# Lab6.net
KiCad netlist of a schematic drawn in Altium Designer
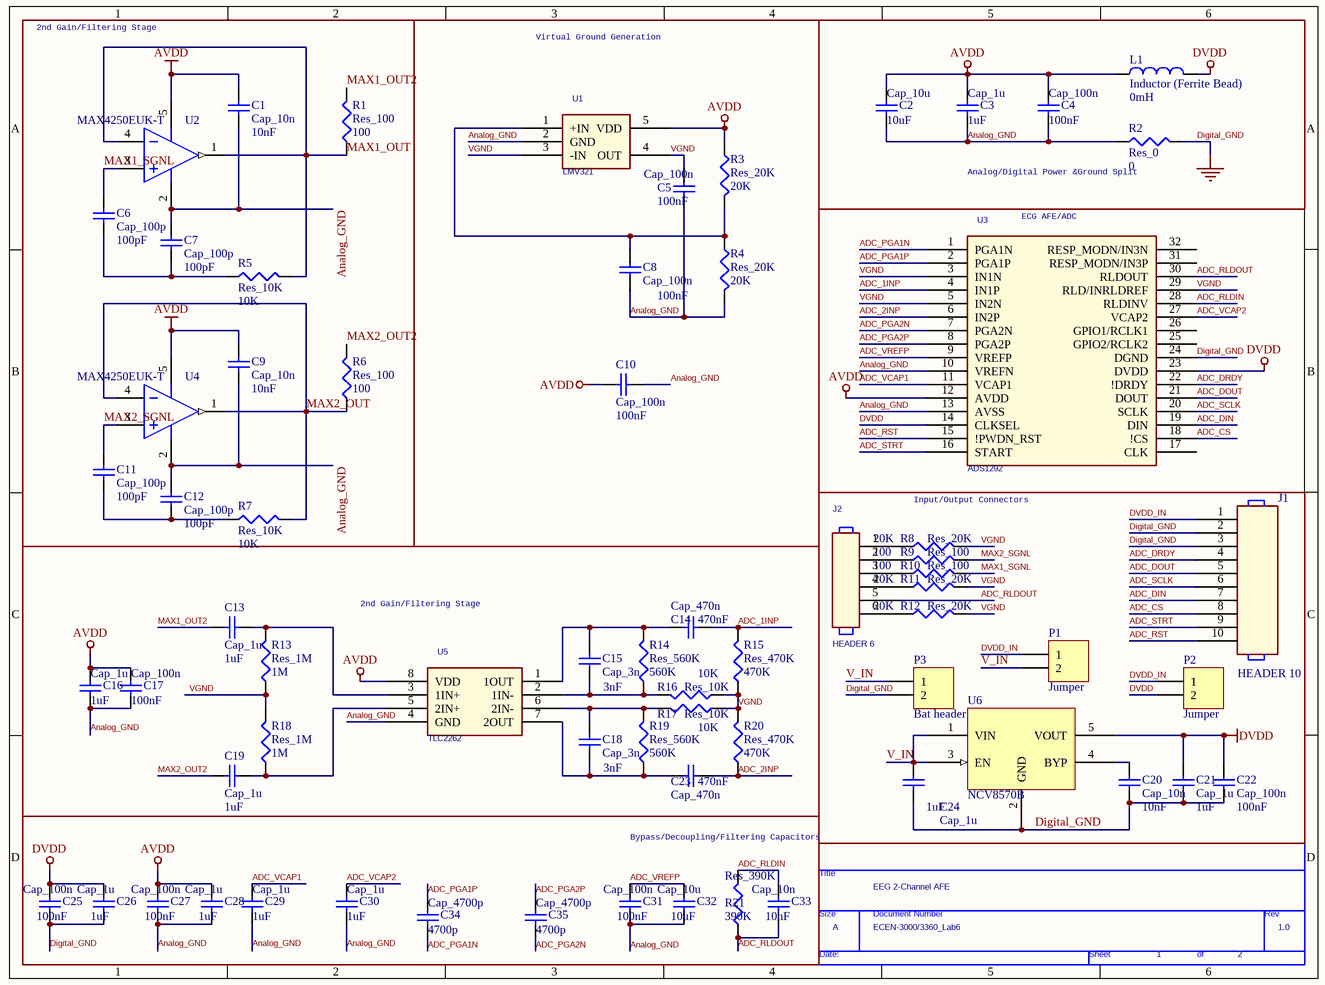
[diagram p0: Lab6.SchDoc]

(export (version "E")
  (design (tool "Eeschema 10.0.6"))
  (components
    (comp (ref "*")
      (value "TitleBlock0")
      (fields
        (field (name "PAGE COUNT") "2")
        (field (name "PAGE NUMBER") "1")
        (field (name "PAGE SIZE") "A")
        (field (name "TITLE") "EEG 2-Channel AFE")
        (field (name "REVCODE") "1.0")
        (field (name "DOC") "ECEN-3000/3360_Lab6")
      )
      (libsource (lib "*") (part "TitleBlock0"))
    )
    (comp (ref "C1")
      (value "Cap_10n")
      (footprint "SMD_0805")
      (description "Capacitor (Semiconductor SIM Model)")
      (fields (field (name "ALTIUM_VALUE") "10nF") (field (name "PUBLISHER") "Altium Limited"))
      (libsource (lib "Miscellaneous Devices") (part "Cap Semi"))
    )
    (comp (ref "C2")
      (value "Cap_10u")
      (footprint "SMD_0805")
      (description "Capacitor (Semiconductor SIM Model)")
      (fields (field (name "ALTIUM_VALUE") "10uF") (field (name "PUBLISHER") "Altium Limited"))
      (libsource (lib "Miscellaneous Devices") (part "Cap Semi"))
    )
    (comp (ref "C3")
      (value "Cap_1u")
      (footprint "SMD_0805")
      (description "Capacitor (Semiconductor SIM Model)")
      (fields (field (name "ALTIUM_VALUE") "1uF") (field (name "PUBLISHER") "Altium Limited"))
      (libsource (lib "Miscellaneous Devices") (part "Cap Semi"))
    )
    (comp (ref "C4")
      (value "Cap_100n")
      (footprint "SMD_0805")
      (description "Capacitor (Semiconductor SIM Model)")
      (fields (field (name "ALTIUM_VALUE") "100nF") (field (name "PUBLISHER") "Altium Limited"))
      (libsource (lib "Miscellaneous Devices") (part "Cap Semi"))
    )
    (comp (ref "C5")
      (value "Cap_100n")
      (footprint "SMD_0805")
      (description "Capacitor (Semiconductor SIM Model)")
      (fields (field (name "ALTIUM_VALUE") "100nF") (field (name "PUBLISHER") "Altium Limited"))
      (libsource (lib "Miscellaneous Devices") (part "Cap Semi"))
    )
    (comp (ref "C6")
      (value "Cap_100p")
      (footprint "SMD_0805")
      (description "Capacitor (Semiconductor SIM Model)")
      (fields (field (name "ALTIUM_VALUE") "100pF") (field (name "PUBLISHER") "Altium Limited"))
      (libsource (lib "Miscellaneous Devices") (part "Cap Semi"))
    )
    (comp (ref "C7")
      (value "Cap_100p")
      (footprint "SMD_0805")
      (description "Capacitor (Semiconductor SIM Model)")
      (fields (field (name "ALTIUM_VALUE") "100pF") (field (name "PUBLISHER") "Altium Limited"))
      (libsource (lib "Miscellaneous Devices") (part "Cap Semi"))
    )
    (comp (ref "C8")
      (value "Cap_100n")
      (footprint "SMD_0805")
      (description "Capacitor (Semiconductor SIM Model)")
      (fields (field (name "ALTIUM_VALUE") "100nF") (field (name "PUBLISHER") "Altium Limited"))
      (libsource (lib "Miscellaneous Devices") (part "Cap Semi"))
    )
    (comp (ref "C9")
      (value "Cap_10n")
      (footprint "SMD_0805")
      (description "Capacitor (Semiconductor SIM Model)")
      (fields (field (name "ALTIUM_VALUE") "10nF") (field (name "PUBLISHER") "Altium Limited"))
      (libsource (lib "Miscellaneous Devices") (part "Cap Semi"))
    )
    (comp (ref "C10")
      (value "Cap_100n")
      (footprint "SMD_0805")
      (description "Capacitor (Semiconductor SIM Model)")
      (fields (field (name "ALTIUM_VALUE") "100nF") (field (name "PUBLISHER") "Altium Limited"))
      (libsource (lib "Miscellaneous Devices") (part "Cap Semi"))
    )
    (comp (ref "C11")
      (value "Cap_100p")
      (footprint "SMD_0805")
      (description "Capacitor (Semiconductor SIM Model)")
      (fields (field (name "ALTIUM_VALUE") "100pF") (field (name "PUBLISHER") "Altium Limited"))
      (libsource (lib "Miscellaneous Devices") (part "Cap Semi"))
    )
    (comp (ref "C12")
      (value "Cap_100p")
      (footprint "SMD_0805")
      (description "Capacitor (Semiconductor SIM Model)")
      (fields (field (name "ALTIUM_VALUE") "100pF") (field (name "PUBLISHER") "Altium Limited"))
      (libsource (lib "Miscellaneous Devices") (part "Cap Semi"))
    )
    (comp (ref "C13")
      (value "Cap_1u")
      (footprint "SMD_0805")
      (description "Capacitor (Semiconductor SIM Model)")
      (fields (field (name "ALTIUM_VALUE") "1uF") (field (name "PUBLISHER") "Altium Limited"))
      (libsource (lib "Miscellaneous Devices") (part "Cap Semi"))
    )
    (comp (ref "C14")
      (value "Cap_470n")
      (footprint "SMD_0805")
      (description "Capacitor (Semiconductor SIM Model)")
      (fields (field (name "ALTIUM_VALUE") "470nF") (field (name "PUBLISHER") "Altium Limited"))
      (libsource (lib "Miscellaneous Devices") (part "Cap Semi"))
    )
    (comp (ref "C15")
      (value "Cap_3n")
      (footprint "SMD_0805")
      (description "Capacitor (Semiconductor SIM Model)")
      (fields (field (name "ALTIUM_VALUE") "3nF") (field (name "PUBLISHER") "Altium Limited"))
      (libsource (lib "Miscellaneous Devices") (part "Cap Semi"))
    )
    (comp (ref "C16")
      (value "Cap_1u")
      (footprint "SMD_0805")
      (description "Capacitor (Semiconductor SIM Model)")
      (fields (field (name "ALTIUM_VALUE") "1uF") (field (name "PUBLISHER") "Altium Limited"))
      (libsource (lib "Miscellaneous Devices") (part "Cap Semi"))
    )
    (comp (ref "C17")
      (value "Cap_100n")
      (footprint "SMD_0805")
      (description "Capacitor (Semiconductor SIM Model)")
      (fields (field (name "ALTIUM_VALUE") "100nF") (field (name "PUBLISHER") "Altium Limited"))
      (libsource (lib "Miscellaneous Devices") (part "Cap Semi"))
    )
    (comp (ref "C18")
      (value "Cap_3n")
      (footprint "SMD_0805")
      (description "Capacitor (Semiconductor SIM Model)")
      (fields (field (name "ALTIUM_VALUE") "3nF") (field (name "PUBLISHER") "Altium Limited"))
      (libsource (lib "Miscellaneous Devices") (part "Cap Semi"))
    )
    (comp (ref "C19")
      (value "Cap_1u")
      (footprint "SMD_0805")
      (description "Capacitor (Semiconductor SIM Model)")
      (fields (field (name "ALTIUM_VALUE") "1uF") (field (name "PUBLISHER") "Altium Limited"))
      (libsource (lib "Miscellaneous Devices") (part "Cap Semi"))
    )
    (comp (ref "C20")
      (value "Cap_10n")
      (footprint "SMD_0805")
      (description "Capacitor (Semiconductor SIM Model)")
      (fields (field (name "ALTIUM_VALUE") "10nF") (field (name "PUBLISHER") "Altium Limited"))
      (libsource (lib "Miscellaneous Devices") (part "Cap Semi"))
    )
    (comp (ref "C21")
      (value "Cap_1u")
      (footprint "SMD_0805")
      (description "Capacitor (Semiconductor SIM Model)")
      (fields (field (name "ALTIUM_VALUE") "1uF") (field (name "PUBLISHER") "Altium Limited"))
      (libsource (lib "Miscellaneous Devices") (part "Cap Semi"))
    )
    (comp (ref "C22")
      (value "Cap_100n")
      (footprint "SMD_0805")
      (description "Capacitor (Semiconductor SIM Model)")
      (fields (field (name "ALTIUM_VALUE") "100nF") (field (name "PUBLISHER") "Altium Limited"))
      (libsource (lib "Miscellaneous Devices") (part "Cap Semi"))
    )
    (comp (ref "C23")
      (value "Cap_470n")
      (footprint "SMD_0805")
      (description "Capacitor (Semiconductor SIM Model)")
      (fields (field (name "ALTIUM_VALUE") "470nF") (field (name "PUBLISHER") "Altium Limited"))
      (libsource (lib "Miscellaneous Devices") (part "Cap Semi"))
    )
    (comp (ref "C24")
      (value "Cap_1u")
      (footprint "SMD_0805")
      (description "Capacitor (Semiconductor SIM Model)")
      (fields (field (name "ALTIUM_VALUE") "1uF") (field (name "PUBLISHER") "Altium Limited"))
      (libsource (lib "Miscellaneous Devices") (part "Cap Semi"))
    )
    (comp (ref "C25")
      (value "Cap_100n")
      (footprint "SMD_0805")
      (description "Capacitor (Semiconductor SIM Model)")
      (fields (field (name "ALTIUM_VALUE") "100nF") (field (name "PUBLISHER") "Altium Limited"))
      (libsource (lib "Miscellaneous Devices") (part "Cap Semi"))
    )
    (comp (ref "C26")
      (value "Cap_1u")
      (footprint "SMD_0805")
      (description "Capacitor (Semiconductor SIM Model)")
      (fields (field (name "ALTIUM_VALUE") "1uF") (field (name "PUBLISHER") "Altium Limited"))
      (libsource (lib "Miscellaneous Devices") (part "Cap Semi"))
    )
    (comp (ref "C27")
      (value "Cap_100n")
      (footprint "SMD_0805")
      (description "Capacitor (Semiconductor SIM Model)")
      (fields (field (name "ALTIUM_VALUE") "100nF") (field (name "PUBLISHER") "Altium Limited"))
      (libsource (lib "Miscellaneous Devices") (part "Cap Semi"))
    )
    (comp (ref "C28")
      (value "Cap_1u")
      (footprint "SMD_0805")
      (description "Capacitor (Semiconductor SIM Model)")
      (fields (field (name "ALTIUM_VALUE") "1uF") (field (name "PUBLISHER") "Altium Limited"))
      (libsource (lib "Miscellaneous Devices") (part "Cap Semi"))
    )
    (comp (ref "C29")
      (value "Cap_1u")
      (footprint "SMD_0805")
      (description "Capacitor (Semiconductor SIM Model)")
      (fields (field (name "ALTIUM_VALUE") "1uF") (field (name "PUBLISHER") "Altium Limited"))
      (libsource (lib "Miscellaneous Devices") (part "Cap Semi"))
    )
    (comp (ref "C30")
      (value "Cap_1u")
      (footprint "SMD_0805")
      (description "Capacitor (Semiconductor SIM Model)")
      (fields (field (name "ALTIUM_VALUE") "1uF") (field (name "PUBLISHER") "Altium Limited"))
      (libsource (lib "Miscellaneous Devices") (part "Cap Semi"))
    )
    (comp (ref "C31")
      (value "Cap_100n")
      (footprint "SMD_0805")
      (description "Capacitor (Semiconductor SIM Model)")
      (fields (field (name "ALTIUM_VALUE") "100nF") (field (name "PUBLISHER") "Altium Limited"))
      (libsource (lib "Miscellaneous Devices") (part "Cap Semi"))
    )
    (comp (ref "C32")
      (value "Cap_10u")
      (footprint "SMD_0805")
      (description "Capacitor (Semiconductor SIM Model)")
      (fields (field (name "ALTIUM_VALUE") "10uF") (field (name "PUBLISHER") "Altium Limited"))
      (libsource (lib "Miscellaneous Devices") (part "Cap Semi"))
    )
    (comp (ref "C33")
      (value "Cap_10n")
      (footprint "SMD_0805")
      (description "Capacitor (Semiconductor SIM Model)")
      (fields (field (name "ALTIUM_VALUE") "10nF") (field (name "PUBLISHER") "Altium Limited"))
      (libsource (lib "Miscellaneous Devices") (part "Cap Semi"))
    )
    (comp (ref "C34")
      (value "Cap_4700p")
      (footprint "SMD_0805")
      (description "Capacitor (Semiconductor SIM Model)")
      (fields (field (name "ALTIUM_VALUE") "4700p") (field (name "PUBLISHER") "Altium Limited"))
      (libsource (lib "Miscellaneous Devices") (part "Cap Semi"))
    )
    (comp (ref "C35")
      (value "Cap_4700p")
      (footprint "SMD_0805")
      (description "Capacitor (Semiconductor SIM Model)")
      (fields (field (name "ALTIUM_VALUE") "4700p") (field (name "PUBLISHER") "Altium Limited"))
      (libsource (lib "Miscellaneous Devices") (part "Cap Semi"))
    )
    (comp (ref "J1")
      (value "HEADER 10")
      (footprint "HDR1X10")
      (libsource (lib "LAB6_Library") (part "HEADER 10"))
    )
    (comp (ref "J2") (value "HEADER 6") (footprint "HDR1X6") (libsource (lib "*") (part "HEADER 6")))
    (comp (ref "L1")
      (value "Inductor (Ferrite Bead)")
      (footprint "SMD_0805")
      (description "Inductor")
      (fields (field (name "ALTIUM_VALUE") "0mH") (field (name "PUBLISHER") "Altium Limited"))
      (libsource (lib "Miscellaneous Devices") (part "Inductor"))
    )
    (comp (ref "P1")
      (value "Jumper")
      (footprint "HDR1X2")
      (description "Header, 2-Pin")
      (fields (field (name "PUBLISHER") "Altium Limited"))
      (libsource (lib "Miscellaneous Connectors") (part "Header 2"))
    )
    (comp (ref "P2")
      (value "Jumper")
      (footprint "HDR1X2")
      (description "Header, 2-Pin")
      (fields (field (name "PUBLISHER") "Altium Limited"))
      (libsource (lib "Miscellaneous Connectors") (part "Header 2"))
    )
    (comp (ref "P3")
      (value "Bat header")
      (footprint "HDR1X2")
      (description "Header, 2-Pin")
      (fields (field (name "PUBLISHER") "Altium Limited"))
      (libsource (lib "Miscellaneous Connectors") (part "Header 2"))
    )
    (comp (ref "R1")
      (value "Res_100")
      (footprint "SMD_0805")
      (description "R_subject_decouple")
      (fields (field (name "ALTIUM_VALUE") "100") (field (name "PUBLISHER") "Altium Limited"))
      (libsource (lib "Miscellaneous Devices") (part "Res3"))
    )
    (comp (ref "R2")
      (value "Res_0")
      (footprint "SMD_0805")
      (description "Resistor")
      (fields (field (name "ALTIUM_VALUE") "0") (field (name "PUBLISHER") "Altium Limited"))
      (libsource (lib "Miscellaneous Devices") (part "Res3"))
    )
    (comp (ref "R3")
      (value "Res_20K")
      (footprint "SMD_0805")
      (description "Resistor")
      (fields (field (name "ALTIUM_VALUE") "20K") (field (name "PUBLISHER") "Altium Limited"))
      (libsource (lib "Miscellaneous Devices") (part "Res3"))
    )
    (comp (ref "R4")
      (value "Res_20K")
      (footprint "SMD_0805")
      (description "Resistor")
      (fields (field (name "ALTIUM_VALUE") "20K") (field (name "PUBLISHER") "Altium Limited"))
      (libsource (lib "Miscellaneous Devices") (part "Res3"))
    )
    (comp (ref "R5")
      (value "Res_10K")
      (footprint "SMD_0805")
      (description "Resistor")
      (fields (field (name "ALTIUM_VALUE") "10K") (field (name "PUBLISHER") "Altium Limited"))
      (libsource (lib "Miscellaneous Devices") (part "Res3"))
    )
    (comp (ref "R6")
      (value "Res_100")
      (footprint "SMD_0805")
      (description "R_subject_decouple")
      (fields (field (name "ALTIUM_VALUE") "100") (field (name "PUBLISHER") "Altium Limited"))
      (libsource (lib "Miscellaneous Devices") (part "Res3"))
    )
    (comp (ref "R7")
      (value "Res_10K")
      (footprint "SMD_0805")
      (description "Resistor")
      (fields (field (name "ALTIUM_VALUE") "10K") (field (name "PUBLISHER") "Altium Limited"))
      (libsource (lib "Miscellaneous Devices") (part "Res3"))
    )
    (comp (ref "R8")
      (value "Res_20K")
      (footprint "SMD_0805")
      (description "Resistor")
      (fields (field (name "ALTIUM_VALUE") "20K") (field (name "PUBLISHER") "Altium Limited"))
      (libsource (lib "Miscellaneous Devices") (part "Res3"))
    )
    (comp (ref "R9")
      (value "Res_100")
      (footprint "SMD_0805")
      (description "Resistor")
      (fields (field (name "ALTIUM_VALUE") "100") (field (name "PUBLISHER") "Altium Limited"))
      (libsource (lib "Miscellaneous Devices") (part "Res3"))
    )
    (comp (ref "R10")
      (value "Res_100")
      (footprint "SMD_0805")
      (description "Resistor")
      (fields (field (name "ALTIUM_VALUE") "100") (field (name "PUBLISHER") "Altium Limited"))
      (libsource (lib "Miscellaneous Devices") (part "Res3"))
    )
    (comp (ref "R11")
      (value "Res_20K")
      (footprint "SMD_0805")
      (description "Resistor")
      (fields (field (name "ALTIUM_VALUE") "20K") (field (name "PUBLISHER") "Altium Limited"))
      (libsource (lib "Miscellaneous Devices") (part "Res3"))
    )
    (comp (ref "R12")
      (value "Res_20K")
      (footprint "SMD_0805")
      (description "Resistor")
      (fields (field (name "ALTIUM_VALUE") "20K") (field (name "PUBLISHER") "Altium Limited"))
      (libsource (lib "Miscellaneous Devices") (part "Res3"))
    )
    (comp (ref "R13")
      (value "Res_1M")
      (footprint "SMD_0805")
      (description "Resistor")
      (fields (field (name "ALTIUM_VALUE") "1M") (field (name "PUBLISHER") "Altium Limited"))
      (libsource (lib "Miscellaneous Devices") (part "Res3"))
    )
    (comp (ref "R14")
      (value "Res_560K")
      (footprint "SMD_0805")
      (description "Resistor")
      (fields (field (name "ALTIUM_VALUE") "560K") (field (name "PUBLISHER") "Altium Limited"))
      (libsource (lib "Miscellaneous Devices") (part "Res3"))
    )
    (comp (ref "R15")
      (value "Res_470K")
      (footprint "SMD_0805")
      (description "Resistor")
      (fields (field (name "ALTIUM_VALUE") "470K") (field (name "PUBLISHER") "Altium Limited"))
      (libsource (lib "Miscellaneous Devices") (part "Res3"))
    )
    (comp (ref "R16")
      (value "Res_10K")
      (footprint "SMD_0805")
      (description "Resistor")
      (fields (field (name "ALTIUM_VALUE") "10K") (field (name "PUBLISHER") "Altium Limited"))
      (libsource (lib "Miscellaneous Devices") (part "Res3"))
    )
    (comp (ref "R17")
      (value "Res_10K")
      (footprint "SMD_0805")
      (description "Resistor")
      (fields (field (name "ALTIUM_VALUE") "10K") (field (name "PUBLISHER") "Altium Limited"))
      (libsource (lib "Miscellaneous Devices") (part "Res3"))
    )
    (comp (ref "R18")
      (value "Res_1M")
      (footprint "SMD_0805")
      (description "Resistor")
      (fields (field (name "ALTIUM_VALUE") "1M") (field (name "PUBLISHER") "Altium Limited"))
      (libsource (lib "Miscellaneous Devices") (part "Res3"))
    )
    (comp (ref "R19")
      (value "Res_560K")
      (footprint "SMD_0805")
      (description "Resistor")
      (fields (field (name "ALTIUM_VALUE") "560K") (field (name "PUBLISHER") "Altium Limited"))
      (libsource (lib "Miscellaneous Devices") (part "Res3"))
    )
    (comp (ref "R20")
      (value "Res_470K")
      (footprint "SMD_0805")
      (description "Resistor")
      (fields (field (name "ALTIUM_VALUE") "470K") (field (name "PUBLISHER") "Altium Limited"))
      (libsource (lib "Miscellaneous Devices") (part "Res3"))
    )
    (comp (ref "R21")
      (value "Res_390K")
      (footprint "SMD_0805")
      (description "Resistor")
      (fields (field (name "ALTIUM_VALUE") "390K") (field (name "PUBLISHER") "Altium Limited"))
      (libsource (lib "Miscellaneous Devices") (part "Res3"))
    )
    (comp (ref "U1") (value "LMV321") (footprint "MAA05A_M") (libsource (lib "*") (part "LMV321")))
    (comp (ref "U2")
      (value "MAX4250EUK-T")
      (footprint "SOT23-5_L")
      (description "SOT23, Single-Supply, Low-Noise, Low-Distortion, Rail-to-Rail Op Amp")
      (fields (field (name "PUBLISHER") "Altium Limited"))
      (libsource (lib "Maxim Operational Amplifier") (part "MAX4250EUK-T"))
    )
    (comp (ref "U3") (value "ADS1292") (footprint "ADS1292_PQFP32") (libsource (lib "*") (part "ADS1292")))
    (comp (ref "U4")
      (value "MAX4250EUK-T")
      (footprint "SOT23-5_L")
      (description "SOT23, Single-Supply, Low-Noise, Low-Distortion, Rail-to-Rail Op Amp")
      (fields (field (name "PUBLISHER") "Altium Limited"))
      (libsource (lib "Maxim Operational Amplifier") (part "MAX4250EUK-T"))
    )
    (comp (ref "U5") (value "TLC2262") (footprint "TLC2262_SOIC8") (libsource (lib "*") (part "TLC2262")))
    (comp (ref "U6")
      (value "NCV8570B")
      (footprint "Lab6:TSOP-5_483-02")
      (libsource (lib "PrototypeV2.0") (part "NCV8570B"))
    )
  )
  (nets
    (net (code "1") (name "/ADC_1INP") (class "Default")
      (node (ref "C14") (pin "1") (pinfunction "1_1") (pintype "passive"))
      (node (ref "R15") (pin "2") (pinfunction "2_2") (pintype "passive"))
      (node (ref "U3") (pin "4") (pinfunction "IN1P_4") (pintype "passive"))
    )
    (net (code "2") (name "/ADC_2INP") (class "Default")
      (node (ref "C23") (pin "1") (pinfunction "1_1") (pintype "passive"))
      (node (ref "R20") (pin "1") (pinfunction "1_1") (pintype "passive"))
      (node (ref "U3") (pin "6") (pinfunction "IN2P_6") (pintype "passive"))
    )
    (net (code "3") (name "/ADC_CS") (class "Default")
      (node (ref "J1") (pin "8") (pinfunction "8_8") (pintype "passive"))
      (node (ref "U3") (pin "18") (pinfunction "!CS_18") (pintype "passive"))
    )
    (net (code "4") (name "/ADC_DIN") (class "Default")
      (node (ref "J1") (pin "7") (pinfunction "7_7") (pintype "passive"))
      (node (ref "U3") (pin "19") (pinfunction "DIN_19") (pintype "passive"))
    )
    (net (code "5") (name "/ADC_DOUT") (class "Default")
      (node (ref "J1") (pin "5") (pinfunction "5_5") (pintype "passive"))
      (node (ref "U3") (pin "21") (pinfunction "DOUT_21") (pintype "passive"))
    )
    (net (code "6") (name "/ADC_DRDY") (class "Default")
      (node (ref "J1") (pin "4") (pinfunction "4_4") (pintype "passive"))
      (node (ref "U3") (pin "22") (pinfunction "!DRDY_22") (pintype "passive"))
    )
    (net (code "7") (name "/ADC_PGA1N") (class "Default")
      (node (ref "C34") (pin "1") (pinfunction "1_1") (pintype "passive"))
      (node (ref "U3") (pin "1") (pinfunction "PGA1N_1") (pintype "passive"))
    )
    (net (code "8") (name "/ADC_PGA1P") (class "Default")
      (node (ref "C34") (pin "2") (pinfunction "2_2") (pintype "passive"))
      (node (ref "U3") (pin "2") (pinfunction "PGA1P_2") (pintype "passive"))
    )
    (net (code "9") (name "/ADC_PGA2N") (class "Default")
      (node (ref "C35") (pin "1") (pinfunction "1_1") (pintype "passive"))
      (node (ref "U3") (pin "7") (pinfunction "PGA2N_7") (pintype "passive"))
    )
    (net (code "10") (name "/ADC_PGA2P") (class "Default")
      (node (ref "C35") (pin "2") (pinfunction "2_2") (pintype "passive"))
      (node (ref "U3") (pin "8") (pinfunction "PGA2P_8") (pintype "passive"))
    )
    (net (code "11") (name "/ADC_RLDIN") (class "Default")
      (node (ref "C33") (pin "2") (pinfunction "2_2") (pintype "passive"))
      (node (ref "R21") (pin "2") (pinfunction "2_2") (pintype "passive"))
      (node (ref "U3") (pin "28") (pinfunction "RLDINV_28") (pintype "passive"))
    )
    (net (code "12") (name "/ADC_RLDOUT") (class "Default")
      (node (ref "C33") (pin "1") (pinfunction "1_1") (pintype "passive"))
      (node (ref "J2") (pin "5") (pinfunction "5_5") (pintype "passive"))
      (node (ref "R21") (pin "1") (pinfunction "1_1") (pintype "passive"))
      (node (ref "U3") (pin "30") (pinfunction "RLDOUT_30") (pintype "passive"))
    )
    (net (code "13") (name "/ADC_RST") (class "Default")
      (node (ref "J1") (pin "10") (pinfunction "10_10") (pintype "passive"))
      (node (ref "U3") (pin "15") (pinfunction "!PWDN_RST_15") (pintype "passive"))
    )
    (net (code "14") (name "/ADC_SCLK") (class "Default")
      (node (ref "J1") (pin "6") (pinfunction "6_6") (pintype "passive"))
      (node (ref "U3") (pin "20") (pinfunction "SCLK_20") (pintype "passive"))
    )
    (net (code "15") (name "/ADC_STRT") (class "Default")
      (node (ref "J1") (pin "9") (pinfunction "9_9") (pintype "passive"))
      (node (ref "U3") (pin "16") (pinfunction "START_16") (pintype "passive"))
    )
    (net (code "16") (name "/ADC_VCAP1") (class "Default")
      (node (ref "C29") (pin "2") (pinfunction "2_2") (pintype "passive"))
      (node (ref "U3") (pin "11") (pinfunction "VCAP1_11") (pintype "passive"))
    )
    (net (code "17") (name "/ADC_VCAP2") (class "Default")
      (node (ref "C30") (pin "2") (pinfunction "2_2") (pintype "passive"))
      (node (ref "U3") (pin "27") (pinfunction "VCAP2_27") (pintype "passive"))
    )
    (net (code "18") (name "/ADC_VREFP") (class "Default")
      (node (ref "C31") (pin "2") (pinfunction "2_2") (pintype "passive"))
      (node (ref "C32") (pin "2") (pinfunction "2_2") (pintype "passive"))
      (node (ref "U3") (pin "9") (pinfunction "VREFP_9") (pintype "passive"))
    )
    (net (code "19") (name "/Analog_GND") (class "Default")
      (node (ref "C1") (pin "1") (pinfunction "1_1") (pintype "passive"))
      (node (ref "C10") (pin "1") (pinfunction "1_1") (pintype "passive"))
      (node (ref "C12") (pin "1") (pinfunction "1_1") (pintype "passive"))
      (node (ref "C16") (pin "1") (pinfunction "1_1") (pintype "passive"))
      (node (ref "C17") (pin "1") (pinfunction "1_1") (pintype "passive"))
      (node (ref "C2") (pin "1") (pinfunction "1_1") (pintype "passive"))
      (node (ref "C27") (pin "1") (pinfunction "1_1") (pintype "passive"))
      (node (ref "C28") (pin "1") (pinfunction "1_1") (pintype "passive"))
      (node (ref "C29") (pin "1") (pinfunction "1_1") (pintype "passive"))
      (node (ref "C3") (pin "1") (pinfunction "1_1") (pintype "passive"))
      (node (ref "C30") (pin "1") (pinfunction "1_1") (pintype "passive"))
      (node (ref "C31") (pin "1") (pinfunction "1_1") (pintype "passive"))
      (node (ref "C32") (pin "1") (pinfunction "1_1") (pintype "passive"))
      (node (ref "C4") (pin "1") (pinfunction "1_1") (pintype "passive"))
      (node (ref "C5") (pin "1") (pinfunction "1_1") (pintype "passive"))
      (node (ref "C7") (pin "1") (pinfunction "1_1") (pintype "passive"))
      (node (ref "C8") (pin "1") (pinfunction "1_1") (pintype "passive"))
      (node (ref "C9") (pin "1") (pinfunction "1_1") (pintype "passive"))
      (node (ref "R2") (pin "1") (pinfunction "1_1") (pintype "passive"))
      (node (ref "R4") (pin "2") (pinfunction "2_2") (pintype "passive"))
      (node (ref "U1") (pin "2") (pinfunction "GND_2") (pintype "passive"))
      (node (ref "U2") (pin "2") (pinfunction "VSS_2") (pintype "power_in"))
      (node (ref "U3") (pin "10") (pinfunction "VREFN_10") (pintype "passive"))
      (node (ref "U3") (pin "13") (pinfunction "AVSS_13") (pintype "passive"))
      (node (ref "U4") (pin "2") (pinfunction "VSS_2") (pintype "power_in"))
      (node (ref "U5") (pin "4") (pinfunction "GND_4") (pintype "passive"))
    )
    (net (code "20") (name "/DVDD_IN") (class "Default")
      (node (ref "J1") (pin "1") (pinfunction "1_1") (pintype "passive"))
      (node (ref "P1") (pin "1") (pinfunction "1_1") (pintype "passive"))
      (node (ref "P2") (pin "1") (pinfunction "1_1") (pintype "passive"))
    )
    (net (code "21") (name "/MAX1_OUT") (class "Default")
      (node (ref "R1") (pin "1") (pinfunction "1_1") (pintype "passive"))
      (node (ref "R5") (pin "2") (pinfunction "2_2") (pintype "passive"))
      (node (ref "U2") (pin "1") (pinfunction "OUT_1") (pintype "output"))
      (node (ref "U2") (pin "4") (pinfunction "IN-_4") (pintype "passive"))
    )
    (net (code "22") (name "/MAX1_OUT2") (class "Default")
      (node (ref "C13") (pin "2") (pinfunction "2_2") (pintype "passive"))
      (node (ref "R1") (pin "2") (pinfunction "2_2") (pintype "passive"))
    )
    (net (code "23") (name "/MAX1_SGNL") (class "Default")
      (node (ref "C6") (pin "1") (pinfunction "1_1") (pintype "passive"))
      (node (ref "R10") (pin "2") (pinfunction "2_2") (pintype "passive"))
      (node (ref "U2") (pin "3") (pinfunction "IN+_3") (pintype "passive"))
    )
    (net (code "24") (name "/MAX2_OUT") (class "Default")
      (node (ref "R6") (pin "1") (pinfunction "1_1") (pintype "passive"))
      (node (ref "R7") (pin "2") (pinfunction "2_2") (pintype "passive"))
      (node (ref "U4") (pin "1") (pinfunction "OUT_1") (pintype "output"))
      (node (ref "U4") (pin "4") (pinfunction "IN-_4") (pintype "passive"))
    )
    (net (code "25") (name "/MAX2_OUT2") (class "Default")
      (node (ref "C19") (pin "2") (pinfunction "2_2") (pintype "passive"))
      (node (ref "R6") (pin "2") (pinfunction "2_2") (pintype "passive"))
    )
    (net (code "26") (name "/MAX2_SGNL") (class "Default")
      (node (ref "C11") (pin "1") (pinfunction "1_1") (pintype "passive"))
      (node (ref "R9") (pin "2") (pinfunction "2_2") (pintype "passive"))
      (node (ref "U4") (pin "3") (pinfunction "IN+_3") (pintype "passive"))
    )
    (net (code "27") (name "/VGND") (class "Default")
      (node (ref "C5") (pin "2") (pinfunction "2_2") (pintype "passive"))
      (node (ref "R11") (pin "2") (pinfunction "2_2") (pintype "passive"))
      (node (ref "R12") (pin "2") (pinfunction "2_2") (pintype "passive"))
      (node (ref "R13") (pin "1") (pinfunction "1_1") (pintype "passive"))
      (node (ref "R15") (pin "1") (pinfunction "1_1") (pintype "passive"))
      (node (ref "R16") (pin "1") (pinfunction "1_1") (pintype "passive"))
      (node (ref "R17") (pin "1") (pinfunction "1_1") (pintype "passive"))
      (node (ref "R18") (pin "2") (pinfunction "2_2") (pintype "passive"))
      (node (ref "R20") (pin "2") (pinfunction "2_2") (pintype "passive"))
      (node (ref "R8") (pin "2") (pinfunction "2_2") (pintype "passive"))
      (node (ref "U1") (pin "3") (pinfunction "-IN_3") (pintype "passive"))
      (node (ref "U1") (pin "4") (pinfunction "OUT_4") (pintype "passive"))
      (node (ref "U3") (pin "29") (pinfunction "RLD/INRLDREF_29") (pintype "passive"))
      (node (ref "U3") (pin "3") (pinfunction "IN1N_3") (pintype "passive"))
      (node (ref "U3") (pin "5") (pinfunction "IN2N_5") (pintype "passive"))
    )
    (net (code "28") (name "/V_IN") (class "Default")
      (node (ref "C24") (pin "2") (pinfunction "2_2") (pintype "passive"))
      (node (ref "P1") (pin "2") (pinfunction "2_2") (pintype "passive"))
      (node (ref "P3") (pin "1") (pinfunction "1_1") (pintype "passive"))
      (node (ref "U6") (pin "1") (pinfunction "VIN_1") (pintype "power_in"))
      (node (ref "U6") (pin "3") (pinfunction "EN_3") (pintype "input"))
    )
    (net (code "29") (name "AVDD") (class "Default")
      (node (ref "C1") (pin "2") (pinfunction "2_2") (pintype "passive"))
      (node (ref "C10") (pin "2") (pinfunction "2_2") (pintype "passive"))
      (node (ref "C16") (pin "2") (pinfunction "2_2") (pintype "passive"))
      (node (ref "C17") (pin "2") (pinfunction "2_2") (pintype "passive"))
      (node (ref "C2") (pin "2") (pinfunction "2_2") (pintype "passive"))
      (node (ref "C27") (pin "2") (pinfunction "2_2") (pintype "passive"))
      (node (ref "C28") (pin "2") (pinfunction "2_2") (pintype "passive"))
      (node (ref "C3") (pin "2") (pinfunction "2_2") (pintype "passive"))
      (node (ref "C4") (pin "2") (pinfunction "2_2") (pintype "passive"))
      (node (ref "C9") (pin "2") (pinfunction "2_2") (pintype "passive"))
      (node (ref "L1") (pin "1") (pinfunction "1_1") (pintype "passive"))
      (node (ref "R3") (pin "1") (pinfunction "1_1") (pintype "passive"))
      (node (ref "U1") (pin "5") (pinfunction "VDD_5") (pintype "passive"))
      (node (ref "U2") (pin "5") (pinfunction "VDD_5") (pintype "power_in"))
      (node (ref "U3") (pin "12") (pinfunction "AVDD_12") (pintype "passive"))
      (node (ref "U4") (pin "5") (pinfunction "VDD_5") (pintype "power_in"))
      (node (ref "U5") (pin "8") (pinfunction "VDD_8") (pintype "passive"))
    )
    (net (code "30") (name "DVDD") (class "Default")
      (node (ref "C21") (pin "2") (pinfunction "2_2") (pintype "passive"))
      (node (ref "C22") (pin "2") (pinfunction "2_2") (pintype "passive"))
      (node (ref "C25") (pin "2") (pinfunction "2_2") (pintype "passive"))
      (node (ref "C26") (pin "2") (pinfunction "2_2") (pintype "passive"))
      (node (ref "L1") (pin "2") (pinfunction "2_2") (pintype "passive"))
      (node (ref "P2") (pin "2") (pinfunction "2_2") (pintype "passive"))
      (node (ref "U3") (pin "14") (pinfunction "CLKSEL_14") (pintype "passive"))
      (node (ref "U3") (pin "23") (pinfunction "DVDD_23") (pintype "passive"))
      (node (ref "U6") (pin "5") (pinfunction "VOUT_5") (pintype "power_in"))
    )
    (net (code "31") (name "GND") (class "Default")
      (node (ref "C20") (pin "1") (pinfunction "1_1") (pintype "passive"))
      (node (ref "C21") (pin "1") (pinfunction "1_1") (pintype "passive"))
      (node (ref "C22") (pin "1") (pinfunction "1_1") (pintype "passive"))
      (node (ref "C24") (pin "1") (pinfunction "1_1") (pintype "passive"))
      (node (ref "C25") (pin "1") (pinfunction "1_1") (pintype "passive"))
      (node (ref "C26") (pin "1") (pinfunction "1_1") (pintype "passive"))
      (node (ref "J1") (pin "2") (pinfunction "2_2") (pintype "passive"))
      (node (ref "J1") (pin "3") (pinfunction "3_3") (pintype "passive"))
      (node (ref "P3") (pin "2") (pinfunction "2_2") (pintype "passive"))
      (node (ref "R2") (pin "2") (pinfunction "2_2") (pintype "passive"))
      (node (ref "U3") (pin "24") (pinfunction "DGND_24") (pintype "passive"))
      (node (ref "U6") (pin "2") (pinfunction "GND_2") (pintype "power_in"))
    )
    (net (code "32") (name "Net-(C6-Pad2)") (class "Default")
      (node (ref "C6") (pin "2") (pinfunction "2_2") (pintype "passive"))
      (node (ref "C7") (pin "2") (pinfunction "2_2") (pintype "passive"))
      (node (ref "R5") (pin "1") (pinfunction "1_1") (pintype "passive"))
    )
    (net (code "33") (name "Net-(C11-Pad2)") (class "Default")
      (node (ref "C11") (pin "2") (pinfunction "2_2") (pintype "passive"))
      (node (ref "C12") (pin "2") (pinfunction "2_2") (pintype "passive"))
      (node (ref "R7") (pin "1") (pinfunction "1_1") (pintype "passive"))
    )
    (net (code "34") (name "Net-(J2-Pad1)") (class "Default")
      (node (ref "J2") (pin "1") (pinfunction "1_1") (pintype "passive"))
      (node (ref "R8") (pin "1") (pinfunction "1_1") (pintype "passive"))
    )
    (net (code "35") (name "Net-(J2-Pad2)") (class "Default")
      (node (ref "J2") (pin "2") (pinfunction "2_2") (pintype "passive"))
      (node (ref "R9") (pin "1") (pinfunction "1_1") (pintype "passive"))
    )
    (net (code "36") (name "Net-(J2-Pad3)") (class "Default")
      (node (ref "J2") (pin "3") (pinfunction "3_3") (pintype "passive"))
      (node (ref "R10") (pin "1") (pinfunction "1_1") (pintype "passive"))
    )
    (net (code "37") (name "Net-(J2-Pad4)") (class "Default")
      (node (ref "J2") (pin "4") (pinfunction "4_4") (pintype "passive"))
      (node (ref "R11") (pin "1") (pinfunction "1_1") (pintype "passive"))
    )
    (net (code "38") (name "Net-(J2-Pad6)") (class "Default")
      (node (ref "J2") (pin "6") (pinfunction "6_6") (pintype "passive"))
      (node (ref "R12") (pin "1") (pinfunction "1_1") (pintype "passive"))
    )
    (net (code "39") (name "Net-(U1-+IN)") (class "Default")
      (node (ref "C8") (pin "2") (pinfunction "2_2") (pintype "passive"))
      (node (ref "R3") (pin "2") (pinfunction "2_2") (pintype "passive"))
      (node (ref "R4") (pin "1") (pinfunction "1_1") (pintype "passive"))
      (node (ref "U1") (pin "1") (pinfunction "+IN_1") (pintype "passive"))
    )
    (net (code "40") (name "Net-(U5-1IN+)") (class "Default")
      (node (ref "C13") (pin "1") (pinfunction "1_1") (pintype "passive"))
      (node (ref "R13") (pin "2") (pinfunction "2_2") (pintype "passive"))
      (node (ref "U5") (pin "3") (pinfunction "1IN+_3") (pintype "passive"))
    )
    (net (code "41") (name "Net-(U5-1IN-)") (class "Default")
      (node (ref "C15") (pin "1") (pinfunction "1_1") (pintype "passive"))
      (node (ref "R14") (pin "1") (pinfunction "1_1") (pintype "passive"))
      (node (ref "R16") (pin "2") (pinfunction "2_2") (pintype "passive"))
      (node (ref "U5") (pin "2") (pinfunction "1IN-_2") (pintype "passive"))
    )
    (net (code "42") (name "Net-(U5-1OUT)") (class "Default")
      (node (ref "C14") (pin "2") (pinfunction "2_2") (pintype "passive"))
      (node (ref "C15") (pin "2") (pinfunction "2_2") (pintype "passive"))
      (node (ref "R14") (pin "2") (pinfunction "2_2") (pintype "passive"))
      (node (ref "U5") (pin "1") (pinfunction "1OUT_1") (pintype "passive"))
    )
    (net (code "43") (name "Net-(U5-2IN+)") (class "Default")
      (node (ref "C19") (pin "1") (pinfunction "1_1") (pintype "passive"))
      (node (ref "R18") (pin "1") (pinfunction "1_1") (pintype "passive"))
      (node (ref "U5") (pin "5") (pinfunction "2IN+_5") (pintype "passive"))
    )
    (net (code "44") (name "Net-(U5-2IN-)") (class "Default")
      (node (ref "C18") (pin "2") (pinfunction "2_2") (pintype "passive"))
      (node (ref "R17") (pin "2") (pinfunction "2_2") (pintype "passive"))
      (node (ref "R19") (pin "2") (pinfunction "2_2") (pintype "passive"))
      (node (ref "U5") (pin "6") (pinfunction "2IN-_6") (pintype "passive"))
    )
    (net (code "45") (name "Net-(U5-2OUT)") (class "Default")
      (node (ref "C18") (pin "1") (pinfunction "1_1") (pintype "passive"))
      (node (ref "C23") (pin "2") (pinfunction "2_2") (pintype "passive"))
      (node (ref "R19") (pin "1") (pinfunction "1_1") (pintype "passive"))
      (node (ref "U5") (pin "7") (pinfunction "2OUT_7") (pintype "passive"))
    )
    (net (code "46") (name "Net-(U6-BYP)") (class "Default")
      (node (ref "C20") (pin "2") (pinfunction "2_2") (pintype "passive"))
      (node (ref "U6") (pin "4") (pinfunction "BYP_4") (pintype "passive"))
    )
    (net (code "47") (name "unconnected-(U3-CLK-Pad17)") (class "Default")
      (node (ref "U3") (pin "17") (pinfunction "CLK_17") (pintype "passive"))
    )
    (net (code "48") (name "unconnected-(U3-GPIO1{slash}RCLK1-Pad26)") (class "Default")
      (node (ref "U3") (pin "26") (pinfunction "GPIO1/RCLK1_26") (pintype "passive"))
    )
    (net (code "49") (name "unconnected-(U3-GPIO2{slash}RCLK2-Pad25)") (class "Default")
      (node (ref "U3") (pin "25") (pinfunction "GPIO2/RCLK2_25") (pintype "passive"))
    )
    (net (code "50") (name "unconnected-(U3-RESP_MODN{slash}IN3N-Pad32)") (class "Default")
      (node (ref "U3") (pin "32") (pinfunction "RESP_MODN/IN3N_32") (pintype "passive"))
    )
    (net (code "51") (name "unconnected-(U3-RESP_MODN{slash}IN3P-Pad31)") (class "Default")
      (node (ref "U3") (pin "31") (pinfunction "RESP_MODN/IN3P_31") (pintype "passive"))
    )
  )
)
